# OneRelayMysensors.net
KiCad netlist of a schematic drawn in EAGLE
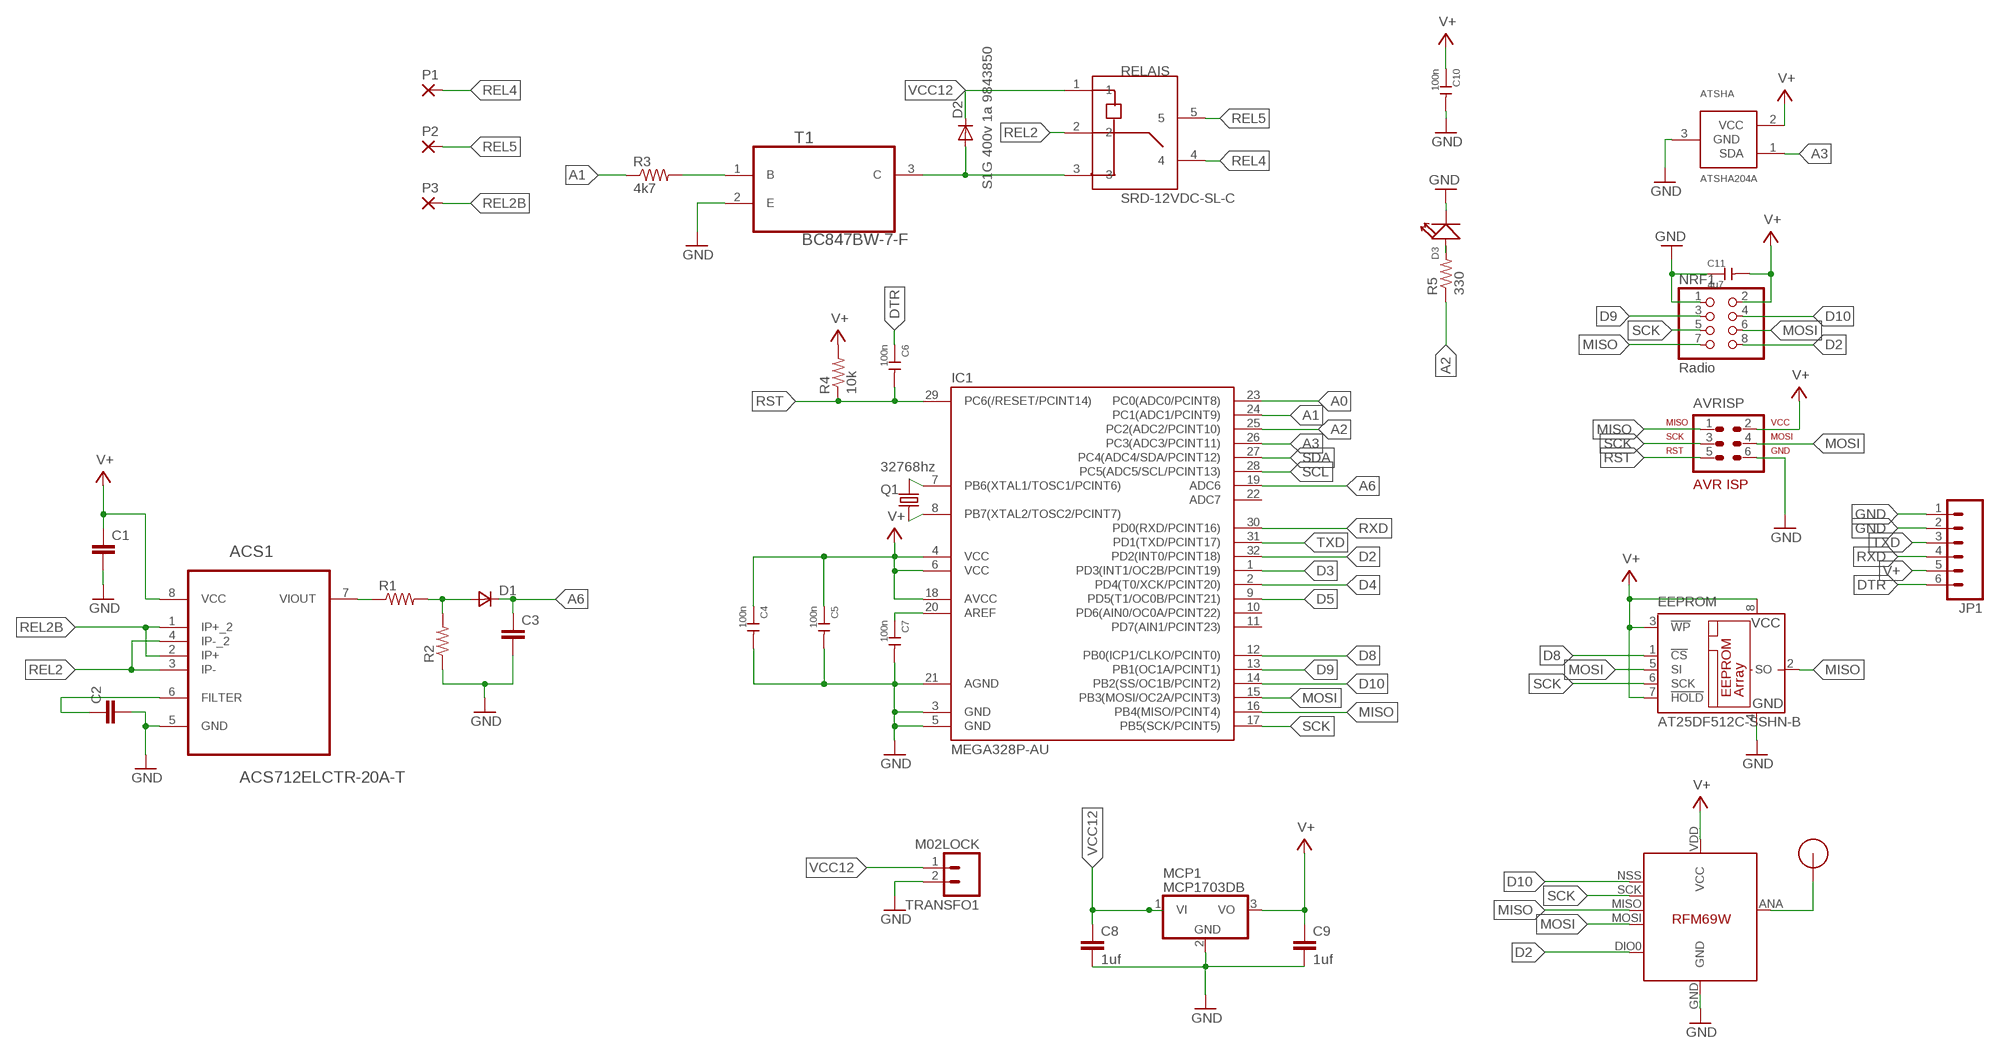
[diagram p0: schematic, sheet 1]

(export (version "E")
  (design (tool "Eeschema 10.0.6"))
  (components
    (comp (ref "$1_28_$")
      (value "RFM12B_ANTENNA")
      (footprint "eagle-import:RFM12B-ANTENNA")
      (libsource (lib "eagle-import") (part "RFM12B_ANTENNA"))
    )
    (comp (ref "ACS1")
      (value "ACS712ELCTR-20A-T")
      (footprint "eagle-import:SOIC127P600X175-8N")
      (libsource (lib "eagle-import") (part "ACS712ELCTR-20A-T"))
    )
    (comp (ref "ATSHA")
      (value "ATSHA204A")
      (footprint "eagle-import:SOT23")
      (libsource (lib "eagle-import") (part "ATSHA204A"))
    )
    (comp (ref "AVRISP")
      (value "AVR-ISP-6VERT")
      (footprint "eagle-import:AVR-ISP-6")
      (libsource (lib "eagle-import") (part "AVR-ISP-6VERT"))
    )
    (comp (ref "C1")
      (value "CAP0805")
      (footprint "eagle-import:0805")
      (libsource (lib "eagle-import") (part "SparkFun-Passives_CAP0805"))
    )
    (comp (ref "C2")
      (value "CAP0805")
      (footprint "eagle-import:0805")
      (libsource (lib "eagle-import") (part "SparkFun-Passives_CAP0805"))
    )
    (comp (ref "C3")
      (value "CAP0805")
      (footprint "eagle-import:0805")
      (libsource (lib "eagle-import") (part "SparkFun-Passives_CAP0805"))
    )
    (comp (ref "C4")
      (value "100n")
      (footprint "eagle-import:C1206")
      (libsource (lib "eagle-import") (part "CAP-1206"))
    )
    (comp (ref "C5")
      (value "100n")
      (footprint "eagle-import:C1206")
      (libsource (lib "eagle-import") (part "CAP-1206"))
    )
    (comp (ref "C6")
      (value "100n")
      (footprint "eagle-import:C1206")
      (libsource (lib "eagle-import") (part "CAP-1206"))
    )
    (comp (ref "C7")
      (value "100n")
      (footprint "eagle-import:C1206")
      (libsource (lib "eagle-import") (part "CAP-1206"))
    )
    (comp (ref "C8")
      (value "1uf")
      (footprint "eagle-import:1206")
      (libsource (lib "eagle-import") (part "CAP1206"))
    )
    (comp (ref "C9")
      (value "1uf")
      (footprint "eagle-import:1206")
      (libsource (lib "eagle-import") (part "CAP1206"))
    )
    (comp (ref "C10")
      (value "100n")
      (footprint "eagle-import:C1206")
      (libsource (lib "eagle-import") (part "CAP-1206"))
    )
    (comp (ref "C11")
      (value "4u7")
      (footprint "eagle-import:C1206")
      (libsource (lib "eagle-import") (part "CAP-1206"))
    )
    (comp (ref "D1")
      (value "DSOD323")
      (footprint "eagle-import:SOD323")
      (fields (field (name "MPN") "CDSOD323-T05C"))
      (libsource (lib "eagle-import") (part "DSOD323"))
    )
    (comp (ref "D2")
      (value "S1G 400v 1a 9843850")
      (footprint "eagle-import:DO214AC")
      (libsource (lib "eagle-import") (part "DIODE-DO214AC"))
    )
    (comp (ref "D3")
      (value "LED-0805")
      (footprint "eagle-import:LED-0805")
      (libsource (lib "eagle-import") (part "LED-0805"))
    )
    (comp (ref "EEPROM")
      (value "AT25DF512C-SSHN-B")
      (footprint "eagle-import:SO-08")
      (fields (field (name "MF") "MICROCHIP") (field (name "MPN") "25AA080/SN"))
      (libsource (lib "eagle-import") (part "25SNAA080"))
    )
    (comp (ref "IC1")
      (value "MEGA328P-AU")
      (footprint "eagle-import:TQFP32-08")
      (libsource (lib "eagle-import") (part "MEGA48/88/168-AU"))
    )
    (comp (ref "JP1")
      (value "M06NO_SILK_FEMALE_PTH")
      (footprint "eagle-import:1X06_NO_SILK")
      (libsource (lib "eagle-import") (part "M06NO_SILK_FEMALE_PTH"))
    )
    (comp (ref "MCP1")
      (value "MCP1703DB")
      (footprint "eagle-import:SOT223")
      (libsource (lib "eagle-import") (part "MCP1703DB"))
    )
    (comp (ref "NRF1")
      (value "Radio")
      (footprint "eagle-import:2X04")
      (libsource (lib "eagle-import") (part "PINHD-2X4"))
    )
    (comp (ref "P1")
      (value "2,54/1,1")
      (footprint "eagle-import:2,54_1,1")
      (libsource (lib "eagle-import") (part "2,54/1,1"))
    )
    (comp (ref "P2")
      (value "2,54/1,1")
      (footprint "eagle-import:2,54_1,1")
      (libsource (lib "eagle-import") (part "2,54/1,1"))
    )
    (comp (ref "P3")
      (value "2,54/1,1")
      (footprint "eagle-import:2,54_1,1")
      (libsource (lib "eagle-import") (part "2,54/1,1"))
    )
    (comp (ref "Q1")
      (value "32768hz")
      (footprint "eagle-import:2P-L3.2XW1.5MM")
      (libsource (lib "eagle-import") (part "CRYSTAL-306010055"))
    )
    (comp (ref "R1")
      (value "RESISTOR0805-RES")
      (footprint "eagle-import:0805")
      (libsource (lib "eagle-import") (part "SparkFun-Resistors_RESISTOR0805-RES"))
    )
    (comp (ref "R2")
      (value "RESISTOR0805-RES")
      (footprint "eagle-import:0805")
      (libsource (lib "eagle-import") (part "SparkFun-Resistors_RESISTOR0805-RES"))
    )
    (comp (ref "R3")
      (value "4k7")
      (footprint "eagle-import:1206")
      (libsource (lib "eagle-import") (part "SparkFun-Resistors_RESISTOR1206"))
    )
    (comp (ref "R4")
      (value "10k")
      (footprint "eagle-import:1206")
      (libsource (lib "eagle-import") (part "RESISTOR1206"))
    )
    (comp (ref "R5")
      (value "330")
      (footprint "eagle-import:1206")
      (libsource (lib "eagle-import") (part "RESISTOR1206"))
    )
    (comp (ref "RELAIS")
      (value "SRD-12VDC-SL-C")
      (footprint "eagle-import:SRD-12VDC-SL-C")
      (libsource (lib "eagle-import") (part "SRD-12VDC-SL-C"))
    )
    (comp (ref "RFM1")
      (value "RFM69")
      (footprint "eagle-import:RFM69W-MINPADS")
      (libsource (lib "eagle-import") (part "RFM69"))
    )
    (comp (ref "T1")
      (value "BC847BW-7-F")
      (footprint "eagle-import:SOT65P210X110-3N")
      (libsource (lib "eagle-import") (part "BC847BW-7-F"))
    )
    (comp (ref "TRANSFO1")
      (value "M02LOCK")
      (footprint "eagle-import:1X02_LOCK")
      (libsource (lib "eagle-import") (part "M02LOCK"))
    )
  )
  (nets
    (net (code "1") (name "A0") (class "Default")
      (node (ref "IC1") (pin "23") (pinfunction "PC0(ADC0/PCINT8)_23") (pintype "bidirectional"))
    )
    (net (code "2") (name "A1") (class "Default")
      (node (ref "IC1") (pin "24") (pinfunction "PC1(ADC1/PCINT9)_24") (pintype "bidirectional"))
      (node (ref "R3") (pin "1") (pinfunction "1_1") (pintype "passive"))
    )
    (net (code "3") (name "A2") (class "Default")
      (node (ref "IC1") (pin "25") (pinfunction "PC2(ADC2/PCINT10)_25") (pintype "bidirectional"))
      (node (ref "R5") (pin "1") (pinfunction "1_1") (pintype "passive"))
    )
    (net (code "4") (name "A3") (class "Default")
      (node (ref "ATSHA") (pin "1") (pinfunction "SDA_1") (pintype "bidirectional"))
      (node (ref "IC1") (pin "26") (pinfunction "PC3(ADC3/PCINT11)_26") (pintype "bidirectional"))
    )
    (net (code "5") (name "A6") (class "Default")
      (node (ref "C3") (pin "1") (pinfunction "1_1") (pintype "passive"))
      (node (ref "D1") (pin "1") (pinfunction "C_1") (pintype "passive"))
      (node (ref "IC1") (pin "19") (pinfunction "ADC6_19") (pintype "passive"))
    )
    (net (code "6") (name "D2") (class "Default")
      (node (ref "IC1") (pin "32") (pinfunction "PD2(INT0/PCINT18)_32") (pintype "bidirectional"))
      (node (ref "NRF1") (pin "8") (pinfunction "8_8") (pintype "passive"))
      (node (ref "RFM1") (pin "DIO0") (pinfunction "DIO0_DIO0") (pintype "open_collector"))
    )
    (net (code "7") (name "D3") (class "Default")
      (node (ref "IC1") (pin "1") (pinfunction "PD3(INT1/OC2B/PCINT19)_1") (pintype "bidirectional"))
    )
    (net (code "8") (name "D4") (class "Default")
      (node (ref "IC1") (pin "2") (pinfunction "PD4(T0/XCK/PCINT20)_2") (pintype "bidirectional"))
    )
    (net (code "9") (name "D5") (class "Default")
      (node (ref "IC1") (pin "9") (pinfunction "PD5(T1/OC0B/PCINT21)_9") (pintype "bidirectional"))
    )
    (net (code "10") (name "D8") (class "Default")
      (node (ref "EEPROM") (pin "1") (pinfunction "~{CS}_1") (pintype "input"))
      (node (ref "IC1") (pin "12") (pinfunction "PB0(ICP1/CLKO/PCINT0)_12") (pintype "bidirectional"))
    )
    (net (code "11") (name "D9") (class "Default")
      (node (ref "IC1") (pin "13") (pinfunction "PB1(OC1A/PCINT1)_13") (pintype "bidirectional"))
      (node (ref "NRF1") (pin "3") (pinfunction "3_3") (pintype "passive"))
    )
    (net (code "12") (name "D10") (class "Default")
      (node (ref "IC1") (pin "14") (pinfunction "PB2(SS/OC1B/PCINT2)_14") (pintype "bidirectional"))
      (node (ref "NRF1") (pin "4") (pinfunction "4_4") (pintype "passive"))
      (node (ref "RFM1") (pin "NSS") (pinfunction "SEL_NSS") (pintype "input"))
    )
    (net (code "13") (name "DTR") (class "Default")
      (node (ref "C6") (pin "1") (pinfunction "1_1") (pintype "passive"))
      (node (ref "JP1") (pin "6") (pinfunction "6_6") (pintype "passive"))
    )
    (net (code "14") (name "GND") (class "Default")
      (node (ref "ACS1") (pin "5") (pinfunction "GND_5") (pintype "passive"))
      (node (ref "ATSHA") (pin "3") (pinfunction "GND_3") (pintype "bidirectional"))
      (node (ref "AVRISP") (pin "6") (pinfunction "6_6") (pintype "passive"))
      (node (ref "C1") (pin "2") (pinfunction "2_2") (pintype "passive"))
      (node (ref "C10") (pin "2") (pinfunction "2_2") (pintype "passive"))
      (node (ref "C11") (pin "1") (pinfunction "1_1") (pintype "passive"))
      (node (ref "C2") (pin "2") (pinfunction "2_2") (pintype "passive"))
      (node (ref "C3") (pin "2") (pinfunction "2_2") (pintype "passive"))
      (node (ref "C4") (pin "2") (pinfunction "2_2") (pintype "passive"))
      (node (ref "C5") (pin "2") (pinfunction "2_2") (pintype "passive"))
      (node (ref "C7") (pin "2") (pinfunction "2_2") (pintype "passive"))
      (node (ref "C8") (pin "2") (pinfunction "2_2") (pintype "passive"))
      (node (ref "C9") (pin "2") (pinfunction "2_2") (pintype "passive"))
      (node (ref "D3") (pin "-") (pinfunction "-_-") (pintype "passive"))
      (node (ref "EEPROM") (pin "4") (pinfunction "GND_4") (pintype "power_in"))
      (node (ref "IC1") (pin "21") (pinfunction "AGND_21") (pintype "power_in"))
      (node (ref "IC1") (pin "3") (pinfunction "GND_3") (pintype "power_in"))
      (node (ref "IC1") (pin "5") (pinfunction "GND_5") (pintype "power_in"))
      (node (ref "JP1") (pin "1") (pinfunction "1_1") (pintype "passive"))
      (node (ref "JP1") (pin "2") (pinfunction "2_2") (pintype "passive"))
      (node (ref "MCP1") (pin "2") (pinfunction "GND_2") (pintype "passive"))
      (node (ref "NRF1") (pin "1") (pinfunction "1_1") (pintype "passive"))
      (node (ref "R2") (pin "1") (pinfunction "1_1") (pintype "passive"))
      (node (ref "RFM1") (pin "GND") (pinfunction "GND_GND") (pintype "power_in"))
      (node (ref "T1") (pin "2") (pinfunction "E_2") (pintype "passive"))
      (node (ref "TRANSFO1") (pin "2") (pinfunction "2_2") (pintype "passive"))
    )
    (net (code "15") (name "MISO") (class "Default")
      (node (ref "AVRISP") (pin "1") (pinfunction "1_1") (pintype "passive"))
      (node (ref "EEPROM") (pin "2") (pinfunction "SO_2") (pintype "bidirectional"))
      (node (ref "IC1") (pin "16") (pinfunction "PB4(MISO/PCINT4)_16") (pintype "bidirectional"))
      (node (ref "NRF1") (pin "7") (pinfunction "7_7") (pintype "passive"))
      (node (ref "RFM1") (pin "MISO") (pinfunction "MISO_MISO") (pintype "input"))
    )
    (net (code "16") (name "MOSI") (class "Default")
      (node (ref "AVRISP") (pin "4") (pinfunction "4_4") (pintype "passive"))
      (node (ref "EEPROM") (pin "5") (pinfunction "SI_5") (pintype "input"))
      (node (ref "IC1") (pin "15") (pinfunction "PB3(MOSI/OC2A/PCINT3)_15") (pintype "bidirectional"))
      (node (ref "NRF1") (pin "6") (pinfunction "6_6") (pintype "passive"))
      (node (ref "RFM1") (pin "MOSI") (pinfunction "MOSI_MOSI") (pintype "output"))
    )
    (net (code "17") (name "Net-($1_28_$-1)") (class "Default")
      (node (ref "$1_28_$") (pin "P$1") (pinfunction "1_P$1") (pintype "bidirectional"))
      (node (ref "RFM1") (pin "ANA") (pinfunction "ANT_ANA") (pintype "passive"))
    )
    (net (code "18") (name "Net-(ACS1-FILTER)") (class "Default")
      (node (ref "ACS1") (pin "6") (pinfunction "FILTER_6") (pintype "input"))
      (node (ref "C2") (pin "1") (pinfunction "1_1") (pintype "passive"))
    )
    (net (code "19") (name "Net-(ACS1-VIOUT)") (class "Default")
      (node (ref "ACS1") (pin "7") (pinfunction "VIOUT_7") (pintype "output"))
      (node (ref "R1") (pin "1") (pinfunction "1_1") (pintype "passive"))
    )
    (net (code "20") (name "Net-(D1-A)") (class "Default")
      (node (ref "D1") (pin "2") (pinfunction "A_2") (pintype "passive"))
      (node (ref "R1") (pin "2") (pinfunction "2_2") (pintype "passive"))
      (node (ref "R2") (pin "2") (pinfunction "2_2") (pintype "passive"))
    )
    (net (code "21") (name "Net-(D3-Pad+)") (class "Default")
      (node (ref "D3") (pin "+") (pinfunction "+_+") (pintype "passive"))
      (node (ref "R5") (pin "2") (pinfunction "2_2") (pintype "passive"))
    )
    (net (code "22") (name "Net-(IC1-AREF)") (class "Default")
      (node (ref "C7") (pin "1") (pinfunction "1_1") (pintype "passive"))
      (node (ref "IC1") (pin "20") (pinfunction "AREF_20") (pintype "passive"))
    )
    (net (code "23") (name "Net-(IC1-PB6(XTAL1{slash}TOSC1{slash}PCINT6))") (class "Default")
      (node (ref "IC1") (pin "7") (pinfunction "PB6(XTAL1/TOSC1/PCINT6)_7") (pintype "bidirectional"))
      (node (ref "Q1") (pin "1") (pinfunction "1_1") (pintype "passive"))
    )
    (net (code "24") (name "Net-(IC1-PB7(XTAL2{slash}TOSC2{slash}PCINT7))") (class "Default")
      (node (ref "IC1") (pin "8") (pinfunction "PB7(XTAL2/TOSC2/PCINT7)_8") (pintype "bidirectional"))
      (node (ref "Q1") (pin "2") (pinfunction "2_2") (pintype "passive"))
    )
    (net (code "25") (name "Net-(T1-B)") (class "Default")
      (node (ref "R3") (pin "2") (pinfunction "2_2") (pintype "passive"))
      (node (ref "T1") (pin "1") (pinfunction "B_1") (pintype "passive"))
    )
    (net (code "26") (name "Net-(T1-C)") (class "Default")
      (node (ref "D2") (pin "A") (pinfunction "A_A") (pintype "passive"))
      (node (ref "RELAIS") (pin "3") (pinfunction "3_3") (pintype "bidirectional"))
      (node (ref "T1") (pin "3") (pinfunction "C_3") (pintype "passive"))
    )
    (net (code "27") (name "REL2") (class "Default")
      (node (ref "ACS1") (pin "3") (pinfunction "IP-_3") (pintype "input"))
      (node (ref "ACS1") (pin "4") (pinfunction "IP-_2_4") (pintype "input"))
      (node (ref "RELAIS") (pin "2") (pinfunction "2_2") (pintype "bidirectional"))
    )
    (net (code "28") (name "REL2B") (class "Default")
      (node (ref "ACS1") (pin "1") (pinfunction "IP+_2_1") (pintype "input"))
      (node (ref "ACS1") (pin "2") (pinfunction "IP+_2") (pintype "input"))
      (node (ref "P3") (pin "1") (pinfunction "P_1") (pintype "passive"))
    )
    (net (code "29") (name "REL4") (class "Default")
      (node (ref "P1") (pin "1") (pinfunction "P_1") (pintype "passive"))
      (node (ref "RELAIS") (pin "4") (pinfunction "4_4") (pintype "bidirectional"))
    )
    (net (code "30") (name "REL5") (class "Default")
      (node (ref "P2") (pin "1") (pinfunction "P_1") (pintype "passive"))
      (node (ref "RELAIS") (pin "5") (pinfunction "5_5") (pintype "bidirectional"))
    )
    (net (code "31") (name "RST") (class "Default")
      (node (ref "AVRISP") (pin "5") (pinfunction "5_5") (pintype "passive"))
      (node (ref "C6") (pin "2") (pinfunction "2_2") (pintype "passive"))
      (node (ref "IC1") (pin "29") (pinfunction "PC6(/RESET/PCINT14)_29") (pintype "bidirectional"))
      (node (ref "R4") (pin "1") (pinfunction "1_1") (pintype "passive"))
    )
    (net (code "32") (name "RXD") (class "Default")
      (node (ref "IC1") (pin "30") (pinfunction "PD0(RXD/PCINT16)_30") (pintype "bidirectional"))
      (node (ref "JP1") (pin "4") (pinfunction "4_4") (pintype "passive"))
    )
    (net (code "33") (name "SCK") (class "Default")
      (node (ref "AVRISP") (pin "3") (pinfunction "3_3") (pintype "passive"))
      (node (ref "EEPROM") (pin "6") (pinfunction "SCK_6") (pintype "input"))
      (node (ref "IC1") (pin "17") (pinfunction "PB5(SCK/PCINT5)_17") (pintype "bidirectional"))
      (node (ref "NRF1") (pin "5") (pinfunction "5_5") (pintype "passive"))
      (node (ref "RFM1") (pin "SCK") (pinfunction "SCK_SCK") (pintype "input"))
    )
    (net (code "34") (name "SCL") (class "Default")
      (node (ref "IC1") (pin "28") (pinfunction "PC5(ADC5/SCL/PCINT13)_28") (pintype "bidirectional"))
    )
    (net (code "35") (name "SDA") (class "Default")
      (node (ref "IC1") (pin "27") (pinfunction "PC4(ADC4/SDA/PCINT12)_27") (pintype "bidirectional"))
    )
    (net (code "36") (name "TXD") (class "Default")
      (node (ref "IC1") (pin "31") (pinfunction "PD1(TXD/PCINT17)_31") (pintype "bidirectional"))
      (node (ref "JP1") (pin "3") (pinfunction "3_3") (pintype "passive"))
    )
    (net (code "37") (name "V+") (class "Default")
      (node (ref "ACS1") (pin "8") (pinfunction "VCC_8") (pintype "power_in"))
      (node (ref "ATSHA") (pin "2") (pinfunction "VCC_2") (pintype "bidirectional"))
      (node (ref "AVRISP") (pin "2") (pinfunction "2_2") (pintype "passive"))
      (node (ref "C1") (pin "1") (pinfunction "1_1") (pintype "passive"))
      (node (ref "C10") (pin "1") (pinfunction "1_1") (pintype "passive"))
      (node (ref "C11") (pin "2") (pinfunction "2_2") (pintype "passive"))
      (node (ref "C4") (pin "1") (pinfunction "1_1") (pintype "passive"))
      (node (ref "C5") (pin "1") (pinfunction "1_1") (pintype "passive"))
      (node (ref "C9") (pin "1") (pinfunction "1_1") (pintype "passive"))
      (node (ref "EEPROM") (pin "3") (pinfunction "~{WP}_3") (pintype "input"))
      (node (ref "EEPROM") (pin "7") (pinfunction "~{HOLD}_7") (pintype "input"))
      (node (ref "EEPROM") (pin "8") (pinfunction "VCC_8") (pintype "power_in"))
      (node (ref "IC1") (pin "18") (pinfunction "AVCC_18") (pintype "passive"))
      (node (ref "IC1") (pin "4") (pinfunction "VCC_4") (pintype "power_in"))
      (node (ref "IC1") (pin "6") (pinfunction "VCC_6") (pintype "power_in"))
      (node (ref "JP1") (pin "5") (pinfunction "5_5") (pintype "passive"))
      (node (ref "MCP1") (pin "3") (pinfunction "VO_3") (pintype "passive"))
      (node (ref "NRF1") (pin "2") (pinfunction "2_2") (pintype "passive"))
      (node (ref "R4") (pin "2") (pinfunction "2_2") (pintype "passive"))
      (node (ref "RFM1") (pin "VDD") (pinfunction "VCC_VDD") (pintype "power_in"))
    )
    (net (code "38") (name "VCC12") (class "Default")
      (node (ref "C8") (pin "1") (pinfunction "1_1") (pintype "passive"))
      (node (ref "D2") (pin "C") (pinfunction "C_C") (pintype "passive"))
      (node (ref "MCP1") (pin "1") (pinfunction "VI_1") (pintype "input"))
      (node (ref "RELAIS") (pin "1") (pinfunction "1_1") (pintype "bidirectional"))
      (node (ref "TRANSFO1") (pin "1") (pinfunction "1_1") (pintype "passive"))
    )
    (net (code "39") (name "unconnected-(IC1-ADC7-Pad22)") (class "Default")
      (node (ref "IC1") (pin "22") (pinfunction "ADC7_22") (pintype "passive"))
    )
    (net (code "40") (name "unconnected-(IC1-PD6(AIN0{slash}OC0A{slash}PCINT22)-Pad10)") (class "Default")
      (node (ref "IC1") (pin "10") (pinfunction "PD6(AIN0/OC0A/PCINT22)_10") (pintype "bidirectional"))
    )
    (net (code "41") (name "unconnected-(IC1-PD7(AIN1{slash}PCINT23)-Pad11)") (class "Default")
      (node (ref "IC1") (pin "11") (pinfunction "PD7(AIN1/PCINT23)_11") (pintype "bidirectional"))
    )
  )
)
